# NeopixelStickOnAStick.net
KiCad netlist of a schematic drawn in EAGLE
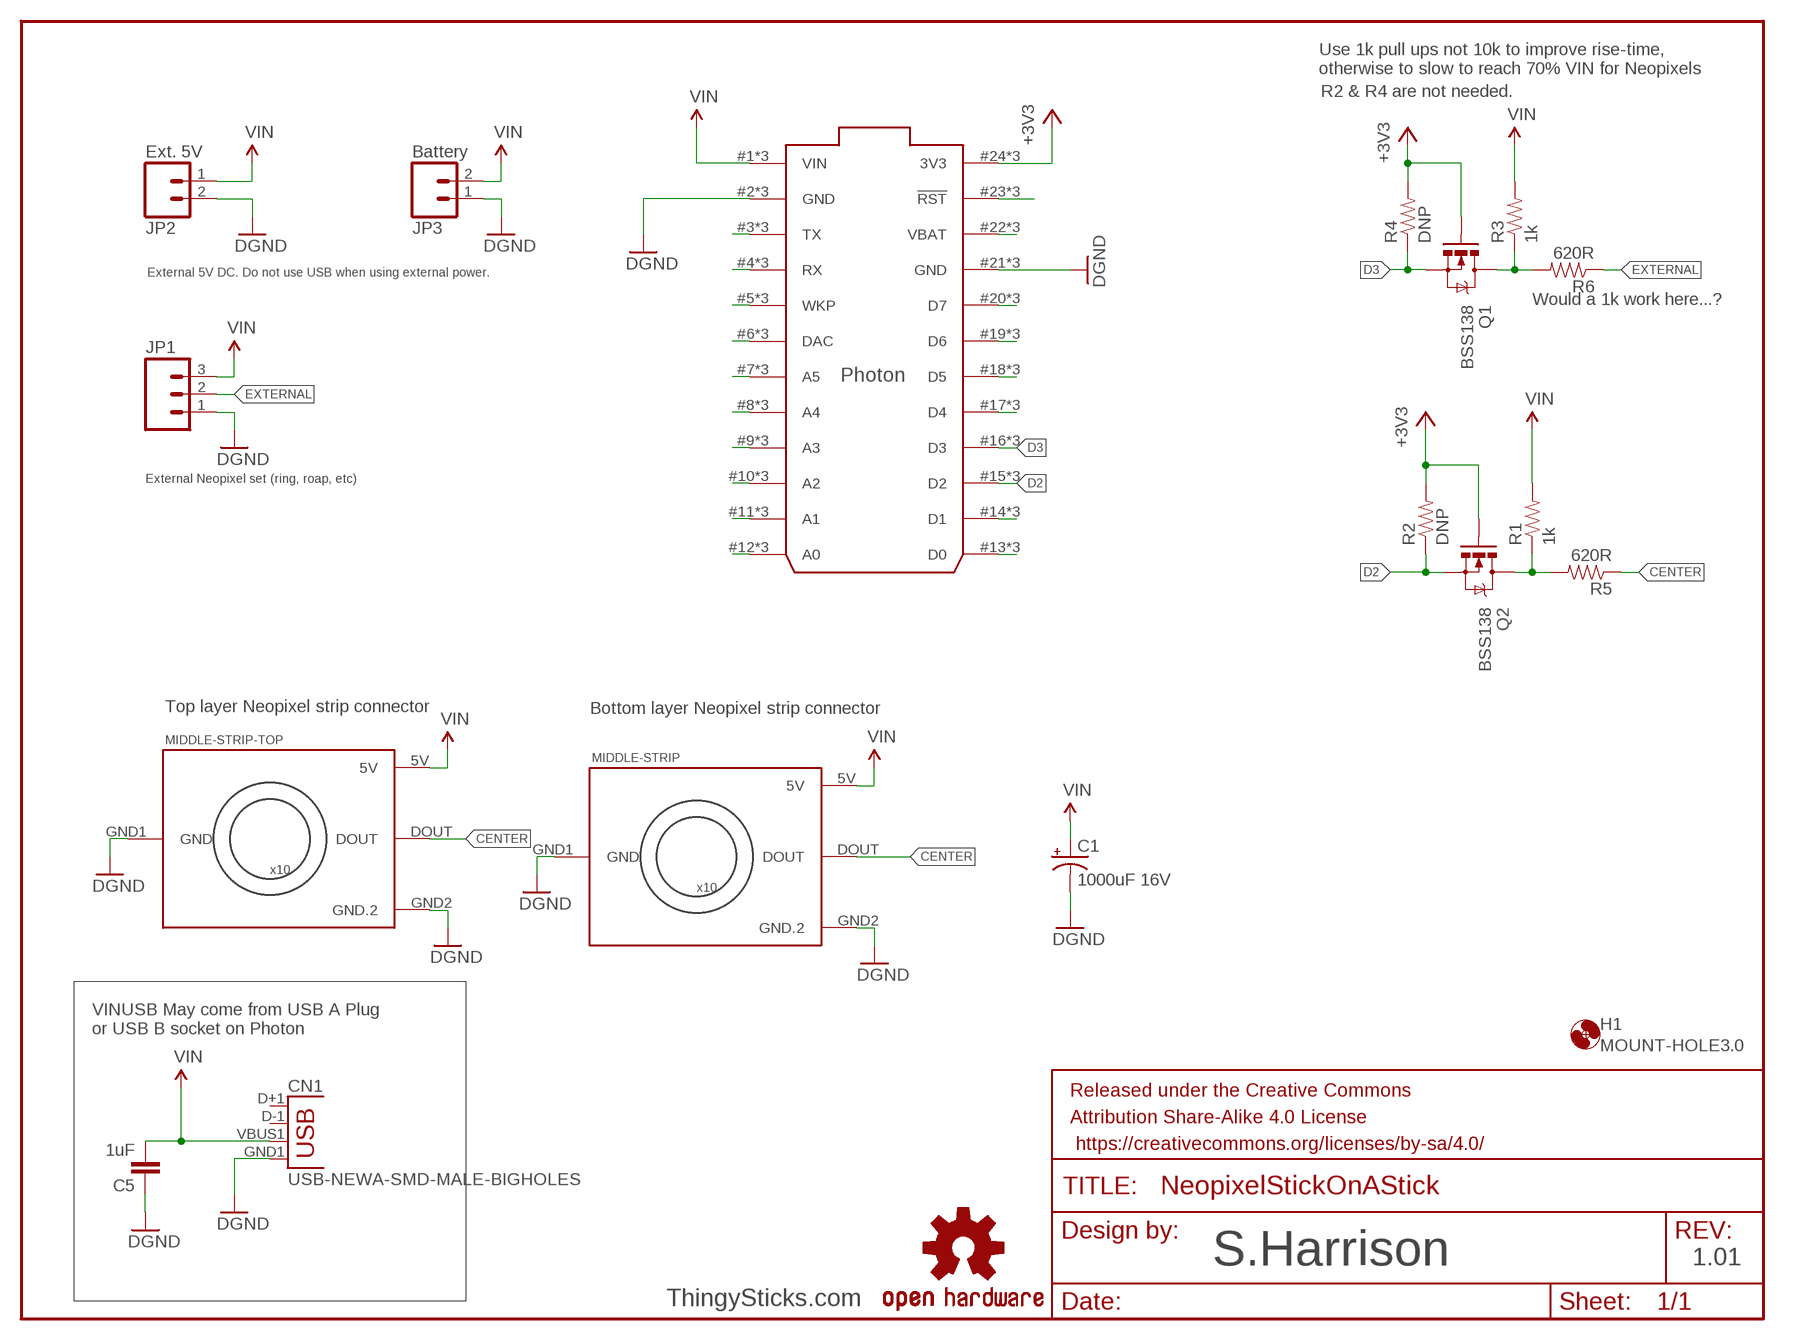
[diagram p0: schematic, sheet 1]

(export (version "E")
  (design (tool "Eeschema 10.0.6"))
  (components
    (comp (ref "C1")
      (value "1000uF 16V")
      (footprint "eagle-import:CPOL-RADIAL-1000UF-25V")
      (libsource (lib "eagle-import") (part "1000UF-25V(PTH)"))
    )
    (comp (ref "C5")
      (value "1uF")
      (footprint "eagle-import:0805")
      (libsource (lib "eagle-import") (part "CAP0805"))
    )
    (comp (ref "CN1")
      (value "USB-NEWA-SMD-MALE-BIGHOLES")
      (footprint "eagle-import:USB-A-SMT-MALE")
      (libsource (lib "eagle-import") (part "USB-NEWA-SMD-MALE-BIGHOLES"))
    )
    (comp (ref "FRAME2")
      (value "FRAME-LETTER")
      (footprint "eagle-import:CREATIVE_COMMONS")
      (libsource (lib "eagle-import") (part "FRAME-LETTER"))
    )
    (comp (ref "H1")
      (value "MOUNT-HOLE3.0")
      (footprint "eagle-import:3,0")
      (libsource (lib "eagle-import") (part "MOUNT-HOLE3.0"))
    )
    (comp (ref "JP1")
      (value "M03POLAR")
      (footprint "eagle-import:MOLEX-1X3")
      (libsource (lib "eagle-import") (part "M03POLAR"))
    )
    (comp (ref "JP2")
      (value "Ext. 5V")
      (footprint "eagle-import:SCREWTERMINAL-3.5MM-2")
      (libsource (lib "eagle-import") (part "M023.5MM"))
    )
    (comp (ref "JP3")
      (value "Battery")
      (footprint "eagle-import:JST-2-SMD")
      (libsource (lib "eagle-import") (part "M02-JST-2MM-SMT"))
    )
    (comp (ref "LOGO2")
      (value "OSHW-LOGOM")
      (footprint "eagle-import:OSHW-LOGO-M")
      (libsource (lib "eagle-import") (part "OSHW-LOGOM"))
    )
    (comp (ref "MIDDLE-STRIP")
      (value "NEOPIXEL-STRIPBOTTOM'")
      (footprint "eagle-import:NEOPIXEL-STRIP")
      (libsource (lib "eagle-import") (part "NEOPIXEL-STRIPBOTTOM'"))
    )
    (comp (ref "MIDDLE-STRIP-TOP")
      (value "NEOPIXEL-STRIPBOTTOM'")
      (footprint "eagle-import:NEOPIXEL-STRIP")
      (libsource (lib "eagle-import") (part "NEOPIXEL-STRIPBOTTOM'"))
    )
    (comp (ref "Q1")
      (value "BSS138")
      (footprint "eagle-import:SOT23-3")
      (libsource (lib "eagle-import") (part "MOSFET-NCHANNELBSS138"))
    )
    (comp (ref "Q2")
      (value "BSS138")
      (footprint "eagle-import:SOT23-3")
      (libsource (lib "eagle-import") (part "MOSFET-NCHANNELBSS138"))
    )
    (comp (ref "R1")
      (value "1k")
      (footprint "eagle-import:1206")
      (libsource (lib "eagle-import") (part "RESISTOR1206"))
    )
    (comp (ref "R2")
      (value "DNP")
      (footprint "eagle-import:1206")
      (libsource (lib "eagle-import") (part "RESISTOR1206"))
    )
    (comp (ref "R3")
      (value "1k")
      (footprint "eagle-import:1206")
      (libsource (lib "eagle-import") (part "RESISTOR1206"))
    )
    (comp (ref "R4")
      (value "DNP")
      (footprint "eagle-import:1206")
      (libsource (lib "eagle-import") (part "RESISTOR1206"))
    )
    (comp (ref "R5")
      (value "620R")
      (footprint "eagle-import:1206")
      (libsource (lib "eagle-import") (part "RESISTOR1206"))
    )
    (comp (ref "R6")
      (value "620R")
      (footprint "eagle-import:1206")
      (libsource (lib "eagle-import") (part "RESISTOR1206"))
    )
    (comp (ref "U$1")
      (value "PHOTON_WITH_STACKABLE_HEADERS")
      (footprint "eagle-import:PHOTON_STACKABLE")
      (libsource (lib "eagle-import") (part "PHOTON_WITH_STACKABLE_HEADERS"))
    )
  )
  (nets
    (net (code "1") (name "+3V3") (class "Default")
      (node (ref "Q1") (pin "1") (pinfunction "G_1") (pintype "passive"))
      (node (ref "Q2") (pin "1") (pinfunction "G_1") (pintype "passive"))
      (node (ref "R2") (pin "2") (pinfunction "2_2") (pintype "passive"))
      (node (ref "R4") (pin "2") (pinfunction "2_2") (pintype "passive"))
      (node (ref "U$1") (pin "#24") (pinfunction "3V3_#24") (pintype "power_in"))
      (node (ref "U$1") (pin "24") (pinfunction "3V3_24") (pintype "power_in"))
      (node (ref "U$1") (pin "@24") (pinfunction "3V3_@24") (pintype "power_in"))
    )
    (net (code "2") (name "CENTER") (class "Default")
      (node (ref "MIDDLE-STRIP") (pin "DOUT") (pinfunction "DOUT_DOUT") (pintype "bidirectional"))
      (node (ref "MIDDLE-STRIP-TOP") (pin "DOUT") (pinfunction "DOUT_DOUT") (pintype "bidirectional"))
      (node (ref "R5") (pin "1") (pinfunction "1_1") (pintype "passive"))
    )
    (net (code "3") (name "D2") (class "Default")
      (node (ref "Q2") (pin "2") (pinfunction "S_2") (pintype "passive"))
      (node (ref "R2") (pin "1") (pinfunction "1_1") (pintype "passive"))
      (node (ref "U$1") (pin "#15") (pinfunction "D2_#15") (pintype "bidirectional"))
      (node (ref "U$1") (pin "15") (pinfunction "D2_15") (pintype "bidirectional"))
      (node (ref "U$1") (pin "@15") (pinfunction "D2_@15") (pintype "bidirectional"))
    )
    (net (code "4") (name "D3") (class "Default")
      (node (ref "Q1") (pin "2") (pinfunction "S_2") (pintype "passive"))
      (node (ref "R4") (pin "1") (pinfunction "1_1") (pintype "passive"))
      (node (ref "U$1") (pin "#16") (pinfunction "D3_#16") (pintype "bidirectional"))
      (node (ref "U$1") (pin "16") (pinfunction "D3_16") (pintype "bidirectional"))
      (node (ref "U$1") (pin "@16") (pinfunction "D3_@16") (pintype "bidirectional"))
    )
    (net (code "5") (name "DGND") (class "Default")
      (node (ref "C1") (pin "-") (pinfunction "-_-") (pintype "passive"))
      (node (ref "C5") (pin "1") (pinfunction "1_1") (pintype "passive"))
      (node (ref "CN1") (pin "GND1") (pinfunction "GND_GND1") (pintype "bidirectional"))
      (node (ref "JP1") (pin "1") (pinfunction "1_1") (pintype "passive"))
      (node (ref "JP2") (pin "2") (pinfunction "2_2") (pintype "passive"))
      (node (ref "JP3") (pin "1") (pinfunction "2_1") (pintype "passive"))
      (node (ref "MIDDLE-STRIP") (pin "GND1") (pinfunction "GND_GND1") (pintype "bidirectional"))
      (node (ref "MIDDLE-STRIP") (pin "GND2") (pinfunction "GND.2_GND2") (pintype "bidirectional"))
      (node (ref "MIDDLE-STRIP-TOP") (pin "GND1") (pinfunction "GND_GND1") (pintype "bidirectional"))
      (node (ref "MIDDLE-STRIP-TOP") (pin "GND2") (pinfunction "GND.2_GND2") (pintype "bidirectional"))
      (node (ref "U$1") (pin "#2") (pinfunction "GND_#2") (pintype "power_in"))
      (node (ref "U$1") (pin "#21") (pinfunction "GND_#21") (pintype "power_in"))
      (node (ref "U$1") (pin "2") (pinfunction "GND_2") (pintype "power_in"))
      (node (ref "U$1") (pin "21") (pinfunction "GND_21") (pintype "power_in"))
      (node (ref "U$1") (pin "@2") (pinfunction "GND_@2") (pintype "power_in"))
      (node (ref "U$1") (pin "@21") (pinfunction "GND_@21") (pintype "power_in"))
    )
    (net (code "6") (name "EXTERNAL") (class "Default")
      (node (ref "JP1") (pin "2") (pinfunction "2_2") (pintype "passive"))
      (node (ref "R6") (pin "1") (pinfunction "1_1") (pintype "passive"))
    )
    (net (code "7") (name "Net-(Q1-D)") (class "Default")
      (node (ref "Q1") (pin "3") (pinfunction "D_3") (pintype "passive"))
      (node (ref "R3") (pin "1") (pinfunction "1_1") (pintype "passive"))
      (node (ref "R6") (pin "2") (pinfunction "2_2") (pintype "passive"))
    )
    (net (code "8") (name "Net-(Q2-D)") (class "Default")
      (node (ref "Q2") (pin "3") (pinfunction "D_3") (pintype "passive"))
      (node (ref "R1") (pin "1") (pinfunction "1_1") (pintype "passive"))
      (node (ref "R5") (pin "2") (pinfunction "2_2") (pintype "passive"))
    )
    (net (code "9") (name "Net-(U$1-A0-Pad#12)") (class "Default")
      (node (ref "U$1") (pin "#12") (pinfunction "A0_#12") (pintype "bidirectional"))
      (node (ref "U$1") (pin "12") (pinfunction "A0_12") (pintype "bidirectional"))
      (node (ref "U$1") (pin "@12") (pinfunction "A0_@12") (pintype "bidirectional"))
    )
    (net (code "10") (name "Net-(U$1-A1-Pad#11)") (class "Default")
      (node (ref "U$1") (pin "#11") (pinfunction "A1_#11") (pintype "bidirectional"))
      (node (ref "U$1") (pin "11") (pinfunction "A1_11") (pintype "bidirectional"))
      (node (ref "U$1") (pin "@11") (pinfunction "A1_@11") (pintype "bidirectional"))
    )
    (net (code "11") (name "Net-(U$1-A2-Pad#10)") (class "Default")
      (node (ref "U$1") (pin "#10") (pinfunction "A2_#10") (pintype "bidirectional"))
      (node (ref "U$1") (pin "10") (pinfunction "A2_10") (pintype "bidirectional"))
      (node (ref "U$1") (pin "@10") (pinfunction "A2_@10") (pintype "bidirectional"))
    )
    (net (code "12") (name "Net-(U$1-A3-Pad#9)") (class "Default")
      (node (ref "U$1") (pin "#9") (pinfunction "A3_#9") (pintype "bidirectional"))
      (node (ref "U$1") (pin "9") (pinfunction "A3_9") (pintype "bidirectional"))
      (node (ref "U$1") (pin "@9") (pinfunction "A3_@9") (pintype "bidirectional"))
    )
    (net (code "13") (name "Net-(U$1-A4-Pad#8)") (class "Default")
      (node (ref "U$1") (pin "#8") (pinfunction "A4_#8") (pintype "bidirectional"))
      (node (ref "U$1") (pin "8") (pinfunction "A4_8") (pintype "bidirectional"))
      (node (ref "U$1") (pin "@8") (pinfunction "A4_@8") (pintype "bidirectional"))
    )
    (net (code "14") (name "Net-(U$1-A5-Pad#7)") (class "Default")
      (node (ref "U$1") (pin "#7") (pinfunction "A5_#7") (pintype "bidirectional"))
      (node (ref "U$1") (pin "7") (pinfunction "A5_7") (pintype "bidirectional"))
      (node (ref "U$1") (pin "@7") (pinfunction "A5_@7") (pintype "bidirectional"))
    )
    (net (code "15") (name "Net-(U$1-D0-Pad#13)") (class "Default")
      (node (ref "U$1") (pin "#13") (pinfunction "D0_#13") (pintype "bidirectional"))
      (node (ref "U$1") (pin "13") (pinfunction "D0_13") (pintype "bidirectional"))
      (node (ref "U$1") (pin "@13") (pinfunction "D0_@13") (pintype "bidirectional"))
    )
    (net (code "16") (name "Net-(U$1-D1-Pad#14)") (class "Default")
      (node (ref "U$1") (pin "#14") (pinfunction "D1_#14") (pintype "bidirectional"))
      (node (ref "U$1") (pin "14") (pinfunction "D1_14") (pintype "bidirectional"))
      (node (ref "U$1") (pin "@14") (pinfunction "D1_@14") (pintype "bidirectional"))
    )
    (net (code "17") (name "Net-(U$1-D4-Pad#17)") (class "Default")
      (node (ref "U$1") (pin "#17") (pinfunction "D4_#17") (pintype "bidirectional"))
      (node (ref "U$1") (pin "17") (pinfunction "D4_17") (pintype "bidirectional"))
      (node (ref "U$1") (pin "@17") (pinfunction "D4_@17") (pintype "bidirectional"))
    )
    (net (code "18") (name "Net-(U$1-D5-Pad#18)") (class "Default")
      (node (ref "U$1") (pin "#18") (pinfunction "D5_#18") (pintype "bidirectional"))
      (node (ref "U$1") (pin "18") (pinfunction "D5_18") (pintype "bidirectional"))
      (node (ref "U$1") (pin "@18") (pinfunction "D5_@18") (pintype "bidirectional"))
    )
    (net (code "19") (name "Net-(U$1-D6-Pad#19)") (class "Default")
      (node (ref "U$1") (pin "#19") (pinfunction "D6_#19") (pintype "bidirectional"))
      (node (ref "U$1") (pin "19") (pinfunction "D6_19") (pintype "bidirectional"))
      (node (ref "U$1") (pin "@19") (pinfunction "D6_@19") (pintype "bidirectional"))
    )
    (net (code "20") (name "Net-(U$1-D7-Pad#20)") (class "Default")
      (node (ref "U$1") (pin "#20") (pinfunction "D7_#20") (pintype "bidirectional"))
      (node (ref "U$1") (pin "20") (pinfunction "D7_20") (pintype "bidirectional"))
      (node (ref "U$1") (pin "@20") (pinfunction "D7_@20") (pintype "bidirectional"))
    )
    (net (code "21") (name "Net-(U$1-DAC-Pad#6)") (class "Default")
      (node (ref "U$1") (pin "#6") (pinfunction "DAC_#6") (pintype "bidirectional"))
      (node (ref "U$1") (pin "6") (pinfunction "DAC_6") (pintype "bidirectional"))
      (node (ref "U$1") (pin "@6") (pinfunction "DAC_@6") (pintype "bidirectional"))
    )
    (net (code "22") (name "Net-(U$1-RX-Pad#4)") (class "Default")
      (node (ref "U$1") (pin "#4") (pinfunction "RX_#4") (pintype "bidirectional"))
      (node (ref "U$1") (pin "4") (pinfunction "RX_4") (pintype "bidirectional"))
      (node (ref "U$1") (pin "@4") (pinfunction "RX_@4") (pintype "bidirectional"))
    )
    (net (code "23") (name "Net-(U$1-TX-Pad#3)") (class "Default")
      (node (ref "U$1") (pin "#3") (pinfunction "TX_#3") (pintype "bidirectional"))
      (node (ref "U$1") (pin "3") (pinfunction "TX_3") (pintype "bidirectional"))
      (node (ref "U$1") (pin "@3") (pinfunction "TX_@3") (pintype "bidirectional"))
    )
    (net (code "24") (name "Net-(U$1-VBAT-Pad#22)") (class "Default")
      (node (ref "U$1") (pin "#22") (pinfunction "VBAT_#22") (pintype "power_in"))
      (node (ref "U$1") (pin "22") (pinfunction "VBAT_22") (pintype "power_in"))
      (node (ref "U$1") (pin "@22") (pinfunction "VBAT_@22") (pintype "power_in"))
    )
    (net (code "25") (name "Net-(U$1-WKP-Pad#5)") (class "Default")
      (node (ref "U$1") (pin "#5") (pinfunction "WKP_#5") (pintype "bidirectional"))
      (node (ref "U$1") (pin "5") (pinfunction "WKP_5") (pintype "bidirectional"))
      (node (ref "U$1") (pin "@5") (pinfunction "WKP_@5") (pintype "bidirectional"))
    )
    (net (code "26") (name "Net-(U$1-~{RST}-Pad#23)") (class "Default")
      (node (ref "U$1") (pin "#23") (pinfunction "~{RST}_#23") (pintype "bidirectional"))
      (node (ref "U$1") (pin "23") (pinfunction "~{RST}_23") (pintype "bidirectional"))
      (node (ref "U$1") (pin "@23") (pinfunction "~{RST}_@23") (pintype "bidirectional"))
    )
    (net (code "27") (name "VIN") (class "Default")
      (node (ref "C1") (pin "+") (pinfunction "+_+") (pintype "passive"))
      (node (ref "C5") (pin "2") (pinfunction "2_2") (pintype "passive"))
      (node (ref "CN1") (pin "VBUS1") (pinfunction "VBUS_VBUS1") (pintype "bidirectional"))
      (node (ref "JP1") (pin "3") (pinfunction "3_3") (pintype "passive"))
      (node (ref "JP2") (pin "1") (pinfunction "1_1") (pintype "passive"))
      (node (ref "JP3") (pin "2") (pinfunction "1_2") (pintype "passive"))
      (node (ref "MIDDLE-STRIP") (pin "5V") (pinfunction "5V_5V") (pintype "bidirectional"))
      (node (ref "MIDDLE-STRIP-TOP") (pin "5V") (pinfunction "5V_5V") (pintype "bidirectional"))
      (node (ref "R1") (pin "2") (pinfunction "2_2") (pintype "passive"))
      (node (ref "R3") (pin "2") (pinfunction "2_2") (pintype "passive"))
      (node (ref "U$1") (pin "#1") (pinfunction "VIN_#1") (pintype "power_in"))
      (node (ref "U$1") (pin "1") (pinfunction "VIN_1") (pintype "power_in"))
      (node (ref "U$1") (pin "@1") (pinfunction "VIN_@1") (pintype "power_in"))
    )
    (net (code "28") (name "unconnected-(CN1-D+-PadD+1)") (class "Default")
      (node (ref "CN1") (pin "D+1") (pinfunction "D+_D+1") (pintype "bidirectional"))
    )
    (net (code "29") (name "unconnected-(CN1-D--PadD-1)") (class "Default")
      (node (ref "CN1") (pin "D-1") (pinfunction "D-_D-1") (pintype "bidirectional"))
    )
  )
)
